# distortion3.net
KiCad netlist of a schematic drawn in EAGLE
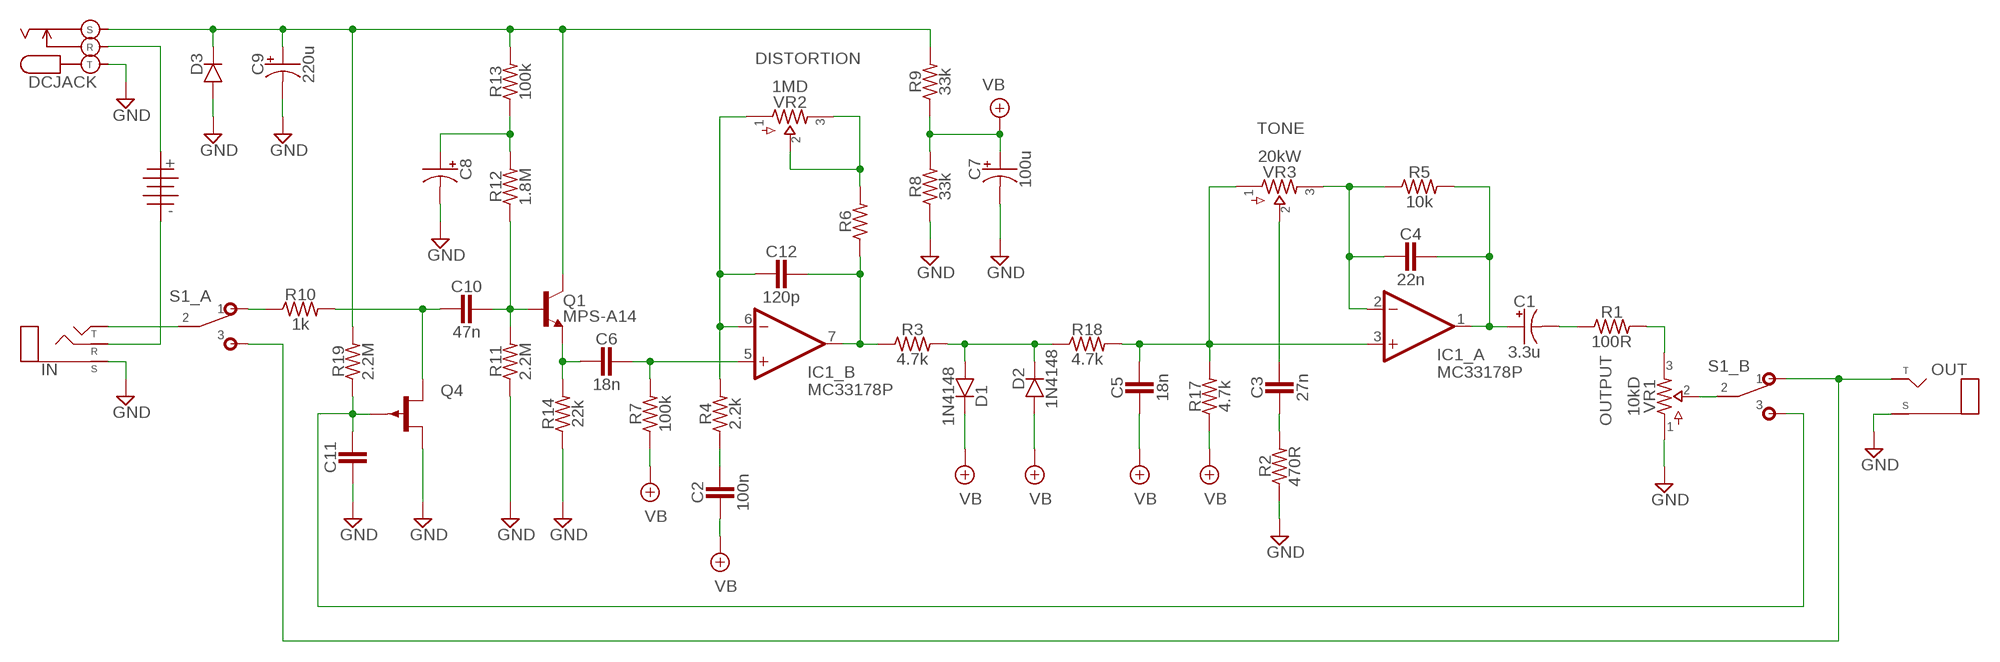
[diagram p0: schematic, sheet 1]

(export (version "E")
  (design (tool "Eeschema 10.0.6"))
  (components
    (comp (ref "BAT1")
      (value "BATTERY")
      (footprint "eagle-import:TWO_PADS")
      (libsource (lib "eagle-import") (part "BATTERY"))
    )
    (comp (ref "C1")
      (value "3.3u")
      (footprint "eagle-import:050_020")
      (libsource (lib "eagle-import") (part "0500"))
    )
    (comp (ref "C2")
      (value "100n")
      (footprint "eagle-import:BOX_SMALL")
      (libsource (lib "eagle-import") (part "CER/FILMBOX.1"))
    )
    (comp (ref "C3")
      (value "27n")
      (footprint "eagle-import:BOX_SMALL")
      (libsource (lib "eagle-import") (part "CER/FILMBOX.1"))
    )
    (comp (ref "C4")
      (value "22n")
      (footprint "eagle-import:BOX_SMALL")
      (libsource (lib "eagle-import") (part "CER/FILMBOX.1"))
    )
    (comp (ref "C5")
      (value "18n")
      (footprint "eagle-import:BOX_SMALL")
      (libsource (lib "eagle-import") (part "CER/FILMBOX.1"))
    )
    (comp (ref "C6")
      (value "18n")
      (footprint "eagle-import:BOX_SMALL")
      (libsource (lib "eagle-import") (part "CER/FILMBOX.1"))
    )
    (comp (ref "C7")
      (value "100u")
      (footprint "eagle-import:050_020")
      (libsource (lib "eagle-import") (part "0500"))
    )
    (comp (ref "C8")
      (value "0500")
      (footprint "eagle-import:050_020")
      (libsource (lib "eagle-import") (part "0500"))
    )
    (comp (ref "C9")
      (value "220u")
      (footprint "eagle-import:050_020")
      (libsource (lib "eagle-import") (part "0500"))
    )
    (comp (ref "C10")
      (value "47n")
      (footprint "eagle-import:BOX_SMALL")
      (libsource (lib "eagle-import") (part "CER/FILMBOX.1"))
    )
    (comp (ref "C11")
      (value "CER/FILMBOX.1")
      (footprint "eagle-import:BOX_SMALL")
      (libsource (lib "eagle-import") (part "CER/FILMBOX.1"))
    )
    (comp (ref "C12")
      (value "120p")
      (footprint "eagle-import:BOX_SMALL")
      (libsource (lib "eagle-import") (part "CER/FILMBOX.1"))
    )
    (comp (ref "D1")
      (value "1N4148")
      (footprint "eagle-import:DO35-2")
      (libsource (lib "eagle-import") (part "DO35.2"))
    )
    (comp (ref "D2")
      (value "1N4148")
      (footprint "eagle-import:DO35-2")
      (libsource (lib "eagle-import") (part "DO35.2"))
    )
    (comp (ref "D3")
      (value "DO35.2")
      (footprint "eagle-import:DO35-2")
      (libsource (lib "eagle-import") (part "DO35.2"))
    )
    (comp (ref "DCJACK")
      (value "DC_KOBICONN")
      (footprint "eagle-import:DC_KOBICONN")
      (libsource (lib "eagle-import") (part "DC_KOBICONN"))
    )
    (comp (ref "IC1")
      (value "MC33178P")
      (footprint "eagle-import:DIL0")
      (libsource (lib "eagle-import") (part "DUALTH"))
    )
    (comp (ref "IN")
      (value "STEREO")
      (footprint "eagle-import:STEREO_PCB")
      (libsource (lib "eagle-import") (part "STEREO"))
    )
    (comp (ref "OUT")
      (value "MONO_JACK")
      (footprint "eagle-import:MONO_SW")
      (libsource (lib "eagle-import") (part "MONO_JACK"))
    )
    (comp (ref "Q1")
      (value "MPS-A14")
      (footprint "eagle-import:TO92-")
      (libsource (lib "eagle-import") (part "2N3904"))
    )
    (comp (ref "Q4")
      (value "2N3820")
      (footprint "eagle-import:TO92F")
      (libsource (lib "eagle-import") (part "2N3820"))
    )
    (comp (ref "R1")
      (value "100R")
      (footprint "eagle-import:R0207_3")
      (libsource (lib "eagle-import") (part "R_.3B"))
    )
    (comp (ref "R2")
      (value "470R")
      (footprint "eagle-import:R0207_3")
      (libsource (lib "eagle-import") (part "R_.3B"))
    )
    (comp (ref "R3")
      (value "4.7k")
      (footprint "eagle-import:R0207_3")
      (libsource (lib "eagle-import") (part "R_.3B"))
    )
    (comp (ref "R4")
      (value "2.2k")
      (footprint "eagle-import:R0207_3")
      (libsource (lib "eagle-import") (part "R_.3B"))
    )
    (comp (ref "R5")
      (value "10k")
      (footprint "eagle-import:R0207_3")
      (libsource (lib "eagle-import") (part "R_.3B"))
    )
    (comp (ref "R6")
      (value "R_.3B")
      (footprint "eagle-import:R0207_3")
      (libsource (lib "eagle-import") (part "R_.3B"))
    )
    (comp (ref "R7")
      (value "100k")
      (footprint "eagle-import:R0207_3")
      (libsource (lib "eagle-import") (part "R_.3B"))
    )
    (comp (ref "R8")
      (value "33k")
      (footprint "eagle-import:R0207_3")
      (libsource (lib "eagle-import") (part "R_.3B"))
    )
    (comp (ref "R9")
      (value "33k")
      (footprint "eagle-import:R0207_3")
      (libsource (lib "eagle-import") (part "R_.3B"))
    )
    (comp (ref "R10")
      (value "1k")
      (footprint "eagle-import:R0207_3")
      (libsource (lib "eagle-import") (part "R_.3B"))
    )
    (comp (ref "R11")
      (value "2.2M")
      (footprint "eagle-import:R0207_3")
      (libsource (lib "eagle-import") (part "R_.3B"))
    )
    (comp (ref "R12")
      (value "1.8M")
      (footprint "eagle-import:R0207_3")
      (libsource (lib "eagle-import") (part "R_.3B"))
    )
    (comp (ref "R13")
      (value "100k")
      (footprint "eagle-import:R0207_3")
      (libsource (lib "eagle-import") (part "R_.3B"))
    )
    (comp (ref "R14")
      (value "22k")
      (footprint "eagle-import:R0207_3")
      (libsource (lib "eagle-import") (part "R_.3B"))
    )
    (comp (ref "R17")
      (value "4.7k")
      (footprint "eagle-import:R0207_3")
      (libsource (lib "eagle-import") (part "R_.3B"))
    )
    (comp (ref "R18")
      (value "4.7k")
      (footprint "eagle-import:R0207_3")
      (libsource (lib "eagle-import") (part "R_.3B"))
    )
    (comp (ref "R19")
      (value "2.2M")
      (footprint "eagle-import:R0207_3")
      (libsource (lib "eagle-import") (part "R_.3B"))
    )
    (comp (ref "S1")
      (value "DPDT")
      (footprint "eagle-import:DPDT")
      (libsource (lib "eagle-import") (part "DPDT"))
    )
    (comp (ref "VR1")
      (value "10kD")
      (footprint "eagle-import:16MM")
      (libsource (lib "eagle-import") (part "POTS16MM"))
    )
    (comp (ref "VR2")
      (value "1MD")
      (footprint "eagle-import:16MM")
      (libsource (lib "eagle-import") (part "POTS16MM"))
    )
    (comp (ref "VR3")
      (value "20kW")
      (footprint "eagle-import:16MM")
      (libsource (lib "eagle-import") (part "POTS16MM"))
    )
  )
  (nets
    (net (code "1") (name "GND") (class "Default")
      (node (ref "C11") (pin "2") (pinfunction "2_2") (pintype "passive"))
      (node (ref "C7") (pin "-") (pinfunction "-_-") (pintype "passive"))
      (node (ref "C8") (pin "-") (pinfunction "-_-") (pintype "passive"))
      (node (ref "C9") (pin "-") (pinfunction "-_-") (pintype "passive"))
      (node (ref "D3") (pin "A") (pinfunction "A_A") (pintype "passive"))
      (node (ref "DCJACK") (pin "T") (pinfunction "T_T") (pintype "bidirectional"))
      (node (ref "IN") (pin "P$1") (pinfunction "S_P$1") (pintype "passive"))
      (node (ref "OUT") (pin "S") (pinfunction "SLEEVE_S") (pintype "passive"))
      (node (ref "Q4") (pin "D") (pinfunction "D_D") (pintype "passive"))
      (node (ref "R11") (pin "1") (pinfunction "1_1") (pintype "passive"))
      (node (ref "R14") (pin "1") (pinfunction "1_1") (pintype "passive"))
      (node (ref "R2") (pin "1") (pinfunction "1_1") (pintype "passive"))
      (node (ref "R8") (pin "1") (pinfunction "1_1") (pintype "passive"))
      (node (ref "VR1") (pin "1") (pinfunction "1_1") (pintype "passive"))
    )
    (net (code "2") (name "Net-(BAT1-P$1)") (class "Default")
      (node (ref "BAT1") (pin "T") (pinfunction "P$1_T") (pintype "bidirectional"))
      (node (ref "DCJACK") (pin "R") (pinfunction "R_R") (pintype "bidirectional"))
    )
    (net (code "3") (name "Net-(BAT1-P$2)") (class "Default")
      (node (ref "BAT1") (pin "S") (pinfunction "P$2_S") (pintype "bidirectional"))
      (node (ref "IN") (pin "P$2") (pinfunction "R_P$2") (pintype "passive"))
    )
    (net (code "4") (name "Net-(C1-Pad-)") (class "Default")
      (node (ref "C1") (pin "-") (pinfunction "-_-") (pintype "passive"))
      (node (ref "R1") (pin "1") (pinfunction "1_1") (pintype "passive"))
    )
    (net (code "5") (name "Net-(C2-Pad2)") (class "Default")
      (node (ref "C2") (pin "2") (pinfunction "2_2") (pintype "passive"))
      (node (ref "R4") (pin "1") (pinfunction "1_1") (pintype "passive"))
    )
    (net (code "6") (name "Net-(C3-Pad1)") (class "Default")
      (node (ref "C3") (pin "1") (pinfunction "1_1") (pintype "passive"))
      (node (ref "R2") (pin "2") (pinfunction "2_2") (pintype "passive"))
    )
    (net (code "7") (name "Net-(C3-Pad2)") (class "Default")
      (node (ref "C3") (pin "2") (pinfunction "2_2") (pintype "passive"))
      (node (ref "VR3") (pin "2") (pinfunction "2_2") (pintype "passive"))
    )
    (net (code "8") (name "Net-(C8-Pad+)") (class "Default")
      (node (ref "C8") (pin "+") (pinfunction "+_+") (pintype "passive"))
      (node (ref "R12") (pin "2") (pinfunction "2_2") (pintype "passive"))
      (node (ref "R13") (pin "1") (pinfunction "1_1") (pintype "passive"))
    )
    (net (code "9") (name "Net-(C10-Pad2)") (class "Default")
      (node (ref "C10") (pin "2") (pinfunction "2_2") (pintype "passive"))
      (node (ref "Q4") (pin "S") (pinfunction "S_S") (pintype "passive"))
      (node (ref "R10") (pin "2") (pinfunction "2_2") (pintype "passive"))
    )
    (net (code "10") (name "Net-(D1-PadA)") (class "Default")
      (node (ref "D1") (pin "A") (pinfunction "A_A") (pintype "passive"))
      (node (ref "D2") (pin "C") (pinfunction "C_C") (pintype "passive"))
      (node (ref "R18") (pin "1") (pinfunction "1_1") (pintype "passive"))
      (node (ref "R3") (pin "2") (pinfunction "2_2") (pintype "passive"))
    )
    (net (code "11") (name "Net-(IC1A-+IN)") (class "Default")
      (node (ref "C5") (pin "2") (pinfunction "2_2") (pintype "passive"))
      (node (ref "IC1") (pin "3") (pinfunction "+IN_3") (pintype "input"))
      (node (ref "R17") (pin "2") (pinfunction "2_2") (pintype "passive"))
      (node (ref "R18") (pin "2") (pinfunction "2_2") (pintype "passive"))
      (node (ref "VR3") (pin "1") (pinfunction "1_1") (pintype "passive"))
    )
    (net (code "12") (name "Net-(IC1A--IN)") (class "Default")
      (node (ref "C4") (pin "1") (pinfunction "1_1") (pintype "passive"))
      (node (ref "IC1") (pin "2") (pinfunction "-IN_2") (pintype "input"))
      (node (ref "R5") (pin "1") (pinfunction "1_1") (pintype "passive"))
      (node (ref "VR3") (pin "3") (pinfunction "3_3") (pintype "passive"))
    )
    (net (code "13") (name "Net-(IC1A-OUT)") (class "Default")
      (node (ref "C1") (pin "+") (pinfunction "+_+") (pintype "passive"))
      (node (ref "C4") (pin "2") (pinfunction "2_2") (pintype "passive"))
      (node (ref "IC1") (pin "1") (pinfunction "OUT_1") (pintype "output"))
      (node (ref "R5") (pin "2") (pinfunction "2_2") (pintype "passive"))
    )
    (net (code "14") (name "Net-(IC1B-+IN)") (class "Default")
      (node (ref "C6") (pin "2") (pinfunction "2_2") (pintype "passive"))
      (node (ref "IC1") (pin "5") (pinfunction "+IN_5") (pintype "input"))
      (node (ref "R7") (pin "2") (pinfunction "2_2") (pintype "passive"))
    )
    (net (code "15") (name "Net-(IC1B--IN)") (class "Default")
      (node (ref "C12") (pin "1") (pinfunction "1_1") (pintype "passive"))
      (node (ref "IC1") (pin "6") (pinfunction "-IN_6") (pintype "input"))
      (node (ref "R4") (pin "2") (pinfunction "2_2") (pintype "passive"))
      (node (ref "VR2") (pin "1") (pinfunction "1_1") (pintype "passive"))
    )
    (net (code "16") (name "Net-(IC1B-OUT)") (class "Default")
      (node (ref "C12") (pin "2") (pinfunction "2_2") (pintype "passive"))
      (node (ref "IC1") (pin "7") (pinfunction "OUT_7") (pintype "output"))
      (node (ref "R3") (pin "1") (pinfunction "1_1") (pintype "passive"))
      (node (ref "R6") (pin "1") (pinfunction "1_1") (pintype "passive"))
    )
    (net (code "17") (name "Net-(IN-T)") (class "Default")
      (node (ref "IN") (pin "P$3") (pinfunction "T_P$3") (pintype "passive"))
      (node (ref "S1") (pin "A2") (pinfunction "2_A2") (pintype "passive"))
    )
    (net (code "18") (name "Net-(OUT-TIP)") (class "Default")
      (node (ref "OUT") (pin "T") (pinfunction "TIP_T") (pintype "passive"))
      (node (ref "S1") (pin "A3") (pinfunction "3_A3") (pintype "passive"))
      (node (ref "S1") (pin "B1") (pinfunction "1_B1") (pintype "passive"))
    )
    (net (code "19") (name "Net-(Q1-B)") (class "Default")
      (node (ref "C10") (pin "1") (pinfunction "1_1") (pintype "passive"))
      (node (ref "Q1") (pin "2") (pinfunction "B_2") (pintype "passive"))
      (node (ref "R11") (pin "2") (pinfunction "2_2") (pintype "passive"))
      (node (ref "R12") (pin "1") (pinfunction "1_1") (pintype "passive"))
    )
    (net (code "20") (name "Net-(Q1-C)") (class "Default")
      (node (ref "C9") (pin "+") (pinfunction "+_+") (pintype "passive"))
      (node (ref "D3") (pin "C") (pinfunction "C_C") (pintype "passive"))
      (node (ref "DCJACK") (pin "S") (pinfunction "S_S") (pintype "bidirectional"))
      (node (ref "Q1") (pin "1") (pinfunction "C_1") (pintype "passive"))
      (node (ref "R13") (pin "2") (pinfunction "2_2") (pintype "passive"))
      (node (ref "R19") (pin "2") (pinfunction "2_2") (pintype "passive"))
      (node (ref "R9") (pin "2") (pinfunction "2_2") (pintype "passive"))
    )
    (net (code "21") (name "Net-(Q1-E)") (class "Default")
      (node (ref "C6") (pin "1") (pinfunction "1_1") (pintype "passive"))
      (node (ref "Q1") (pin "3") (pinfunction "E_3") (pintype "passive"))
      (node (ref "R14") (pin "2") (pinfunction "2_2") (pintype "passive"))
    )
    (net (code "22") (name "Net-(R1-Pad2)") (class "Default")
      (node (ref "R1") (pin "2") (pinfunction "2_2") (pintype "passive"))
      (node (ref "VR1") (pin "3") (pinfunction "3_3") (pintype "passive"))
    )
    (net (code "23") (name "Net-(R6-Pad2)") (class "Default")
      (node (ref "R6") (pin "2") (pinfunction "2_2") (pintype "passive"))
      (node (ref "VR2") (pin "2") (pinfunction "2_2") (pintype "passive"))
      (node (ref "VR2") (pin "3") (pinfunction "3_3") (pintype "passive"))
    )
    (net (code "24") (name "Net-(S1A-1)") (class "Default")
      (node (ref "R10") (pin "1") (pinfunction "1_1") (pintype "passive"))
      (node (ref "S1") (pin "A1") (pinfunction "1_A1") (pintype "passive"))
    )
    (net (code "25") (name "Net-(S1B-2)") (class "Default")
      (node (ref "S1") (pin "B2") (pinfunction "2_B2") (pintype "passive"))
      (node (ref "VR1") (pin "2") (pinfunction "2_2") (pintype "passive"))
    )
    (net (code "26") (name "Net-(S1B-3)") (class "Default")
      (node (ref "C11") (pin "1") (pinfunction "1_1") (pintype "passive"))
      (node (ref "Q4") (pin "G") (pinfunction "G_G") (pintype "passive"))
      (node (ref "R19") (pin "1") (pinfunction "1_1") (pintype "passive"))
      (node (ref "S1") (pin "B3") (pinfunction "3_B3") (pintype "passive"))
    )
    (net (code "27") (name "VB") (class "Default")
      (node (ref "C2") (pin "1") (pinfunction "1_1") (pintype "passive"))
      (node (ref "C5") (pin "1") (pinfunction "1_1") (pintype "passive"))
      (node (ref "C7") (pin "+") (pinfunction "+_+") (pintype "passive"))
      (node (ref "D1") (pin "C") (pinfunction "C_C") (pintype "passive"))
      (node (ref "D2") (pin "A") (pinfunction "A_A") (pintype "passive"))
      (node (ref "R17") (pin "1") (pinfunction "1_1") (pintype "passive"))
      (node (ref "R7") (pin "1") (pinfunction "1_1") (pintype "passive"))
      (node (ref "R8") (pin "2") (pinfunction "2_2") (pintype "passive"))
      (node (ref "R9") (pin "1") (pinfunction "1_1") (pintype "passive"))
    )
  )
)
